# Relay.net
KiCad netlist of a schematic drawn in Altium Designer
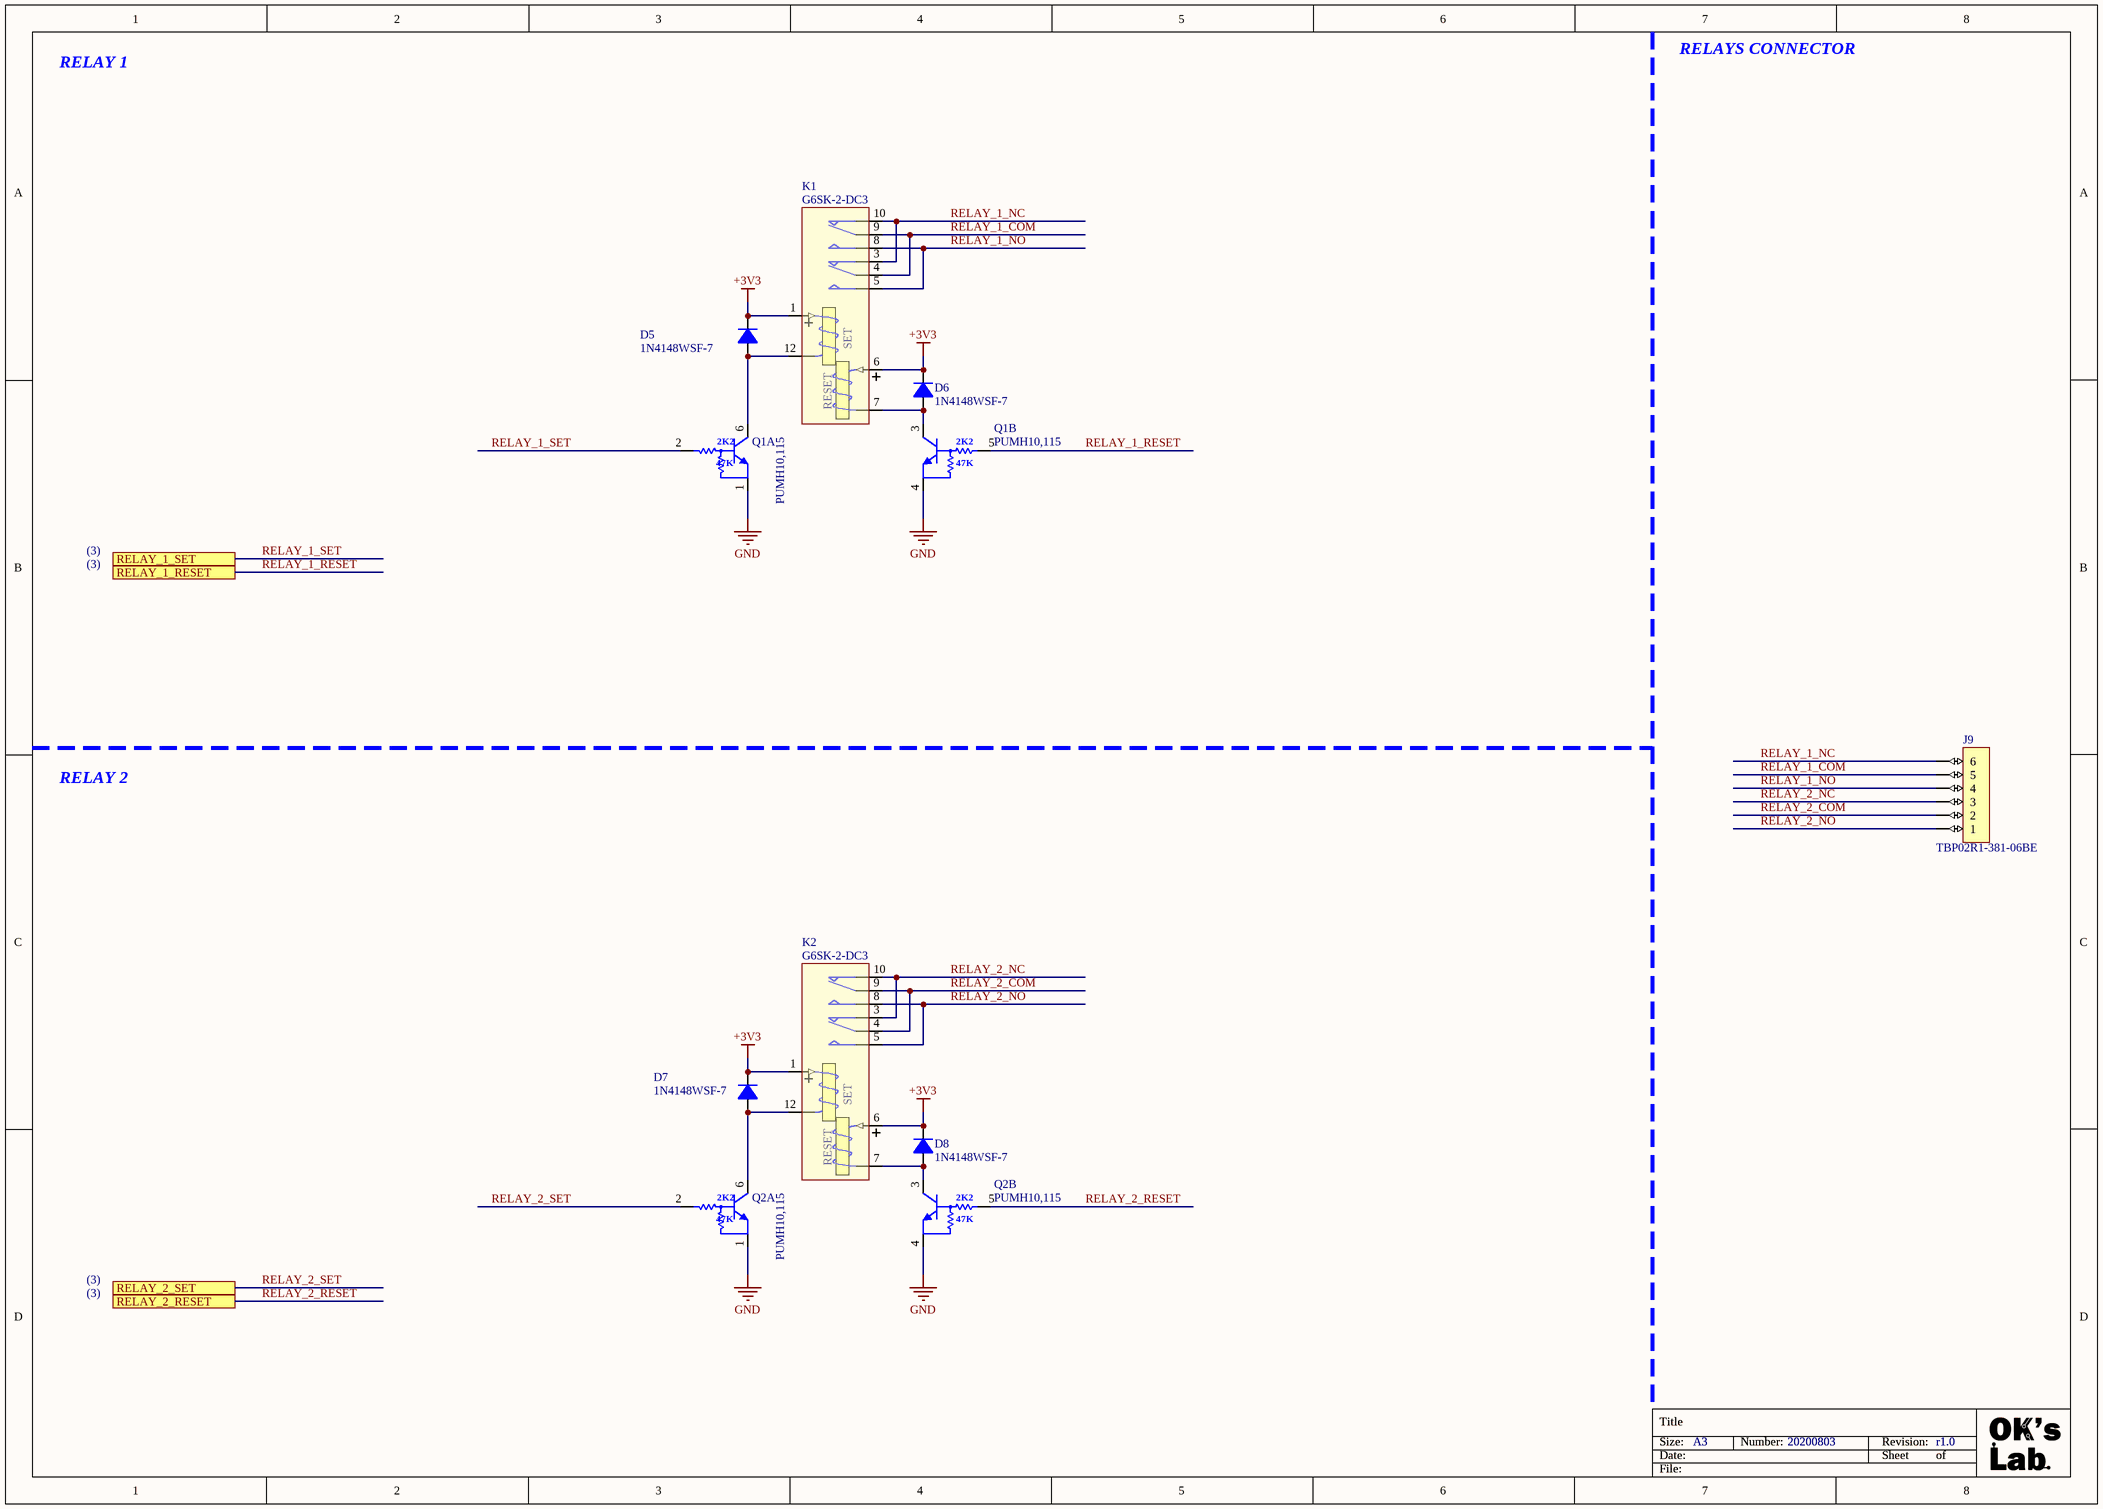
[diagram p0: Relay.SchDoc]

(export (version "E")
  (design (tool "Eeschema 10.0.6"))
  (components
    (comp (ref "D5")
      (value "1N4148WSF-7")
      (footprint "SOD323F__SC90")
      (description "DIODE GEN PURP 100V 250MA SOD323")
      (fields (field (name "MANUFACTURER") "Diodes"))
      (libsource (lib "Altium_Lib") (part "DIODE_1N4148WSF-7"))
    )
    (comp (ref "D6")
      (value "1N4148WSF-7")
      (footprint "SOD323F__SC90")
      (description "DIODE GEN PURP 100V 250MA SOD323")
      (fields (field (name "MANUFACTURER") "Diodes"))
      (libsource (lib "Altium_Lib") (part "DIODE_1N4148WSF-7"))
    )
    (comp (ref "D7")
      (value "1N4148WSF-7")
      (footprint "SOD323F__SC90")
      (description "DIODE GEN PURP 100V 250MA SOD323")
      (fields (field (name "MANUFACTURER") "Diodes"))
      (libsource (lib "Altium_Lib") (part "DIODE_1N4148WSF-7"))
    )
    (comp (ref "D8")
      (value "1N4148WSF-7")
      (footprint "SOD323F__SC90")
      (description "DIODE GEN PURP 100V 250MA SOD323")
      (fields (field (name "MANUFACTURER") "Diodes"))
      (libsource (lib "Altium_Lib") (part "DIODE_1N4148WSF-7"))
    )
    (comp (ref "J9")
      (value "TBP02R1-381-06BE")
      (footprint "CONN_6_POS__TBP02R1-381-06BE")
      (description "TERMINAL BLOCK, PLUGGABLE, 3.81,")
      (fields (field (name "MANUFACTURER") "CUI Devices"))
      (libsource (lib "Altium_Lib") (part "CONN_6_POS__TBP02R1-381-06BE"))
    )
    (comp (ref "K1")
      (value "G6SK-2-DC3")
      (footprint "G6SK-2")
      (description "Telecom Relay DPDT (2 Form C) Through Hole")
      (fields (field (name "MANUFACTURER") "Omron"))
      (libsource (lib "Altium_Lib") (part "RELAY__G6SK-2 DC3"))
    )
    (comp (ref "K2")
      (value "G6SK-2-DC3")
      (footprint "G6SK-2")
      (description "Telecom Relay DPDT (2 Form C) Through Hole")
      (fields (field (name "MANUFACTURER") "Omron"))
      (libsource (lib "Altium_Lib") (part "RELAY__G6SK-2 DC3"))
    )
    (comp (ref "Q1")
      (value "PUMH10,115")
      (footprint "SOT-363")
      (description "TRANS 2NPN PREBIAS 0.3W 6TSSOP")
      (fields (field (name "MANUFACTURER") "Nexperia USA Inc."))
      (libsource (lib "Altium_Lib") (part "PUMH10,115"))
    )
    (comp (ref "Q2")
      (value "PUMH10,115")
      (footprint "SOT-363")
      (description "TRANS 2NPN PREBIAS 0.3W 6TSSOP")
      (fields (field (name "MANUFACTURER") "Nexperia USA Inc."))
      (libsource (lib "Altium_Lib") (part "PUMH10,115"))
    )
  )
  (nets
    (net (code "1") (name "+3V3") (class "Default")
      (node (ref "D5") (pin "2") (pinfunction "K_2") (pintype "passive"))
      (node (ref "D6") (pin "2") (pinfunction "K_2") (pintype "passive"))
      (node (ref "D7") (pin "2") (pinfunction "K_2") (pintype "passive"))
      (node (ref "D8") (pin "2") (pinfunction "K_2") (pintype "passive"))
      (node (ref "K1") (pin "1") (pinfunction "T1_1") (pintype "input"))
      (node (ref "K1") (pin "6") (pinfunction "T1_6") (pintype "input"))
      (node (ref "K2") (pin "1") (pinfunction "T1_1") (pintype "input"))
      (node (ref "K2") (pin "6") (pinfunction "T1_6") (pintype "input"))
    )
    (net (code "2") (name "/RELAY_1_COM") (class "Default")
      (node (ref "J9") (pin "5") (pinfunction "5_5") (pintype "bidirectional"))
      (node (ref "K1") (pin "4") (pinfunction "COM_1_4") (pintype "passive"))
      (node (ref "K1") (pin "9") (pinfunction "COM_2_9") (pintype "passive"))
    )
    (net (code "3") (name "/RELAY_1_NC") (class "Default")
      (node (ref "J9") (pin "6") (pinfunction "6_6") (pintype "bidirectional"))
      (node (ref "K1") (pin "10") (pinfunction "NC_2_10") (pintype "passive"))
      (node (ref "K1") (pin "3") (pinfunction "NC_1_3") (pintype "passive"))
    )
    (net (code "4") (name "/RELAY_1_NO") (class "Default")
      (node (ref "J9") (pin "4") (pinfunction "4_4") (pintype "bidirectional"))
      (node (ref "K1") (pin "5") (pinfunction "NO_1_5") (pintype "passive"))
      (node (ref "K1") (pin "8") (pinfunction "NO_2_8") (pintype "passive"))
    )
    (net (code "5") (name "/RELAY_1_RESET") (class "Default")
      (node (ref "Q1") (pin "5") (pinfunction "B2_5") (pintype "passive"))
    )
    (net (code "6") (name "/RELAY_1_SET") (class "Default")
      (node (ref "Q1") (pin "2") (pinfunction "B1_2") (pintype "passive"))
    )
    (net (code "7") (name "/RELAY_2_COM") (class "Default")
      (node (ref "J9") (pin "2") (pinfunction "2_2") (pintype "bidirectional"))
      (node (ref "K2") (pin "4") (pinfunction "COM_1_4") (pintype "passive"))
      (node (ref "K2") (pin "9") (pinfunction "COM_2_9") (pintype "passive"))
    )
    (net (code "8") (name "/RELAY_2_NC") (class "Default")
      (node (ref "J9") (pin "3") (pinfunction "3_3") (pintype "bidirectional"))
      (node (ref "K2") (pin "10") (pinfunction "NC_2_10") (pintype "passive"))
      (node (ref "K2") (pin "3") (pinfunction "NC_1_3") (pintype "passive"))
    )
    (net (code "9") (name "/RELAY_2_NO") (class "Default")
      (node (ref "J9") (pin "1") (pinfunction "1_1") (pintype "bidirectional"))
      (node (ref "K2") (pin "5") (pinfunction "NO_1_5") (pintype "passive"))
      (node (ref "K2") (pin "8") (pinfunction "NO_2_8") (pintype "passive"))
    )
    (net (code "10") (name "/RELAY_2_RESET") (class "Default")
      (node (ref "Q2") (pin "5") (pinfunction "B2_5") (pintype "passive"))
    )
    (net (code "11") (name "/RELAY_2_SET") (class "Default")
      (node (ref "Q2") (pin "2") (pinfunction "B1_2") (pintype "passive"))
    )
    (net (code "12") (name "GND") (class "Default")
      (node (ref "Q1") (pin "1") (pinfunction "E1_1") (pintype "passive"))
      (node (ref "Q1") (pin "4") (pinfunction "E2_4") (pintype "passive"))
      (node (ref "Q2") (pin "1") (pinfunction "E1_1") (pintype "passive"))
      (node (ref "Q2") (pin "4") (pinfunction "E2_4") (pintype "passive"))
    )
    (net (code "13") (name "Net-(D5-A)") (class "Default")
      (node (ref "D5") (pin "1") (pinfunction "A_1") (pintype "passive"))
      (node (ref "K1") (pin "12") (pinfunction "T2_12") (pintype "passive"))
      (node (ref "Q1") (pin "6") (pinfunction "C1_6") (pintype "passive"))
    )
    (net (code "14") (name "Net-(D6-A)") (class "Default")
      (node (ref "D6") (pin "1") (pinfunction "A_1") (pintype "passive"))
      (node (ref "K1") (pin "7") (pinfunction "T2_7") (pintype "passive"))
      (node (ref "Q1") (pin "3") (pinfunction "C2_3") (pintype "passive"))
    )
    (net (code "15") (name "Net-(D7-A)") (class "Default")
      (node (ref "D7") (pin "1") (pinfunction "A_1") (pintype "passive"))
      (node (ref "K2") (pin "12") (pinfunction "T2_12") (pintype "passive"))
      (node (ref "Q2") (pin "6") (pinfunction "C1_6") (pintype "passive"))
    )
    (net (code "16") (name "Net-(D8-A)") (class "Default")
      (node (ref "D8") (pin "1") (pinfunction "A_1") (pintype "passive"))
      (node (ref "K2") (pin "7") (pinfunction "T2_7") (pintype "passive"))
      (node (ref "Q2") (pin "3") (pinfunction "C2_3") (pintype "passive"))
    )
  )
)
